# EbookReader_Schematic.net
KiCad netlist of a schematic drawn in EAGLE
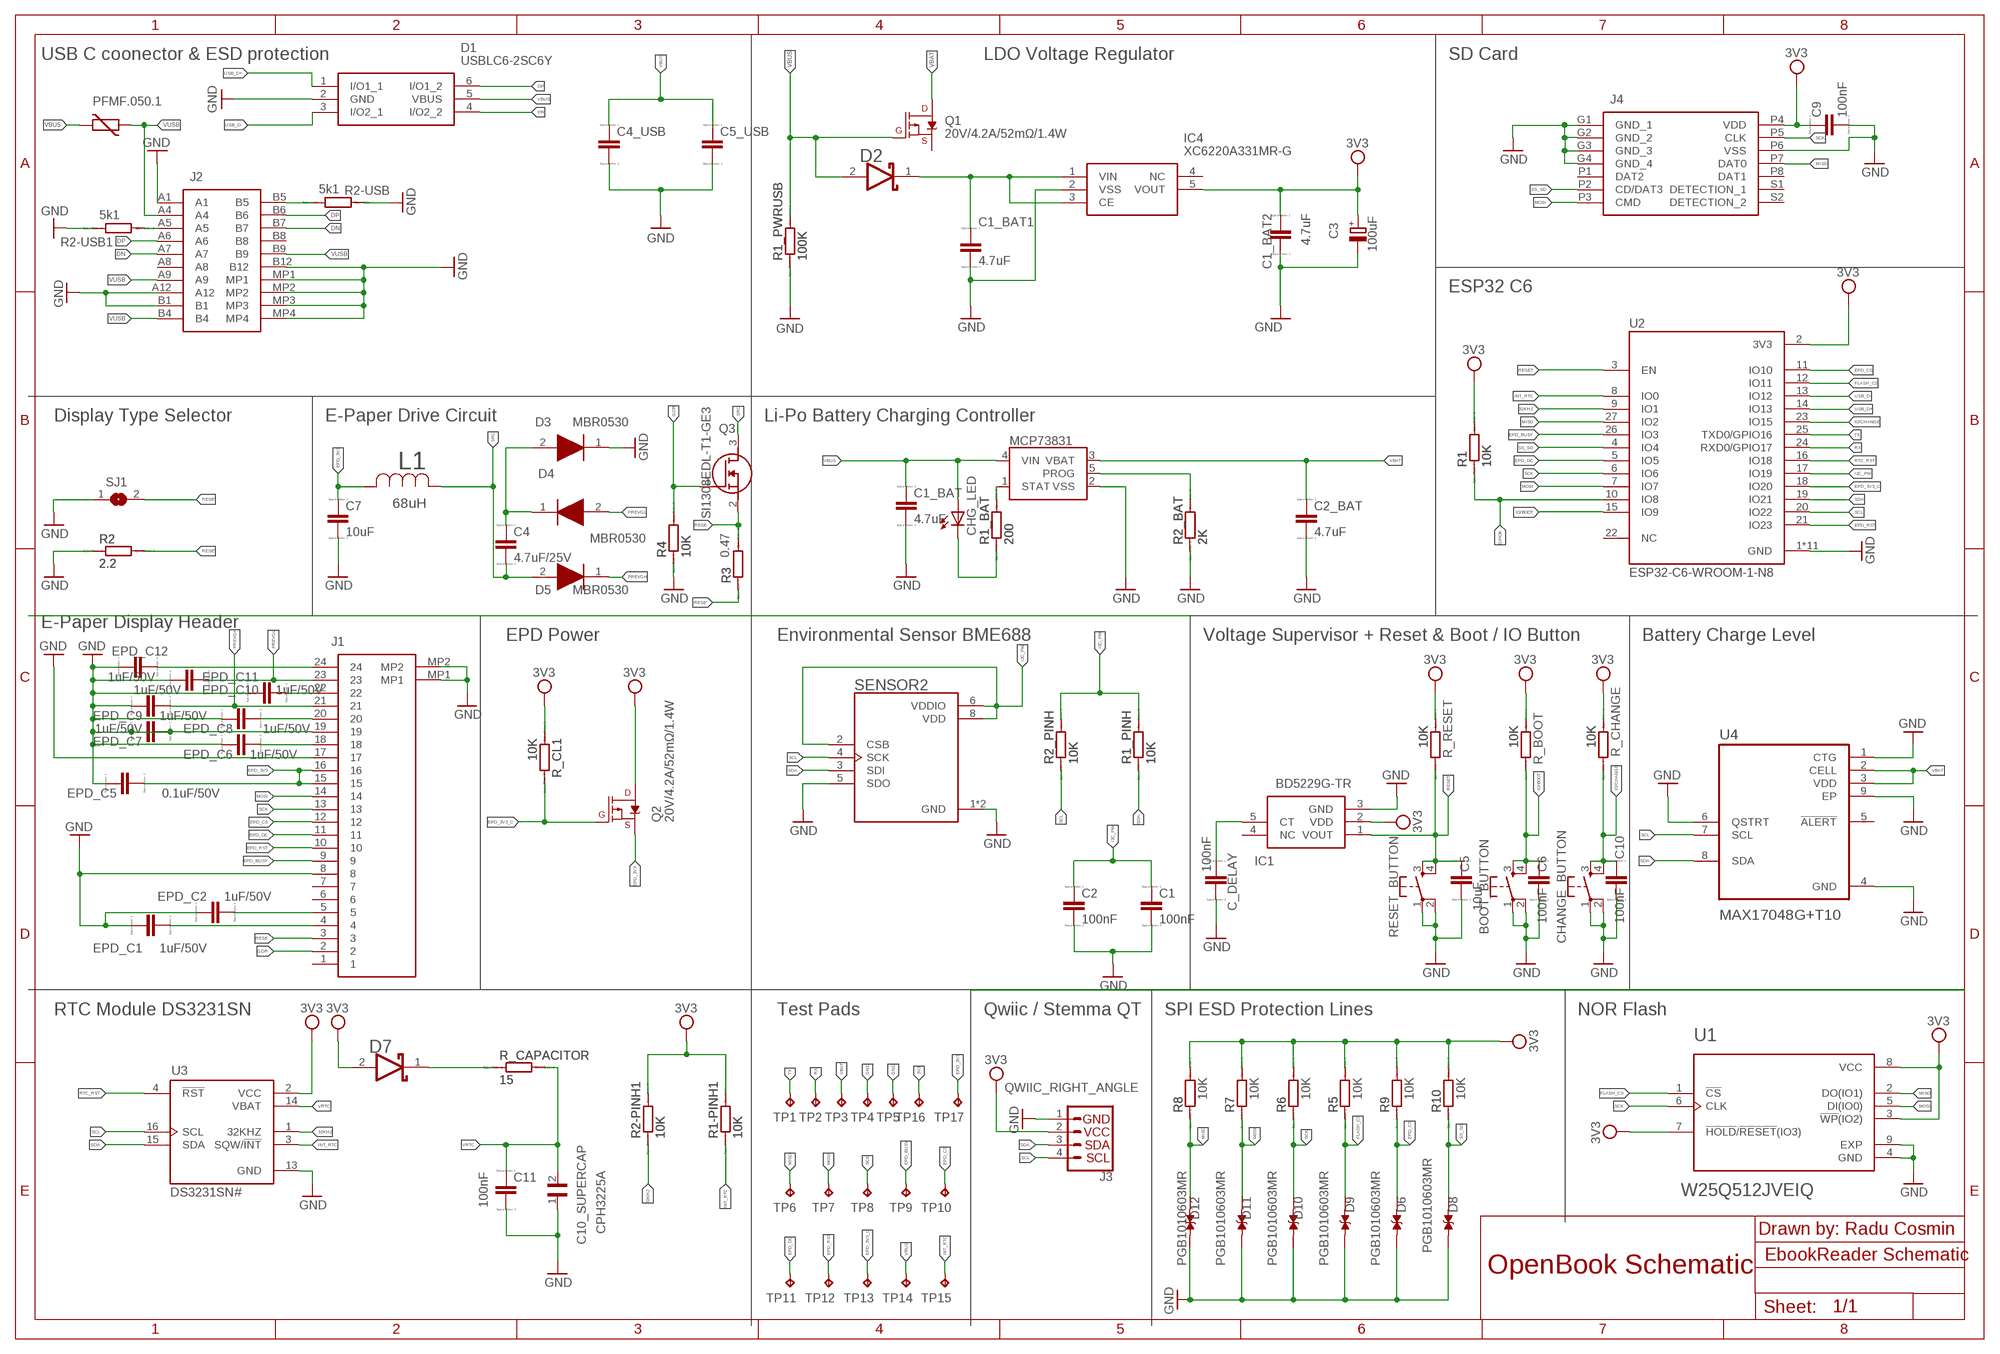
[diagram p0: schematic, sheet 1]

(export (version "E")
  (design (tool "Eeschema 10.0.6"))
  (components
    (comp (ref "BOOT_BUTTON")
      (value "BUTTON_CUSYOMV1")
      (footprint "eagle-import:MYBUTTON")
      (libsource (lib "eagle-import") (part "BUTTON_CUSYOMV1"))
    )
    (comp (ref "C1")
      (value "100nF")
      (footprint "eagle-import:ESP32_WROVER_EAGLE-LTSPICE_C0402")
      (libsource (lib "eagle-import") (part "ESP32_WROVER_EAGLE-LTSPICE_CC0402"))
    )
    (comp (ref "C1_BAT")
      (value "4.7uF")
      (footprint "eagle-import:ESP32_WROVER_EAGLE-LTSPICE_C0402")
      (libsource (lib "eagle-import") (part "ESP32_WROVER_EAGLE-LTSPICE_CC0402"))
    )
    (comp (ref "C1_BAT1")
      (value "4.7uF")
      (footprint "eagle-import:ESP32_WROVER_EAGLE-LTSPICE_C0402")
      (libsource (lib "eagle-import") (part "ESP32_WROVER_EAGLE-LTSPICE_CC0402"))
    )
    (comp (ref "C1_BAT2")
      (value "4.7uF")
      (footprint "eagle-import:ESP32_WROVER_EAGLE-LTSPICE_C0402")
      (libsource (lib "eagle-import") (part "ESP32_WROVER_EAGLE-LTSPICE_CC0402"))
    )
    (comp (ref "C2")
      (value "100nF")
      (footprint "eagle-import:ESP32_WROVER_EAGLE-LTSPICE_C0402")
      (libsource (lib "eagle-import") (part "ESP32_WROVER_EAGLE-LTSPICE_CC0402"))
    )
    (comp (ref "C2_BAT")
      (value "4.7uF")
      (footprint "eagle-import:ESP32_WROVER_EAGLE-LTSPICE_C0402")
      (libsource (lib "eagle-import") (part "ESP32_WROVER_EAGLE-LTSPICE_CC0402"))
    )
    (comp (ref "C3")
      (value "100uF")
      (footprint "eagle-import:RCL_CT3528")
      (libsource (lib "eagle-import") (part "RCL_CPOL-EUCT3528"))
    )
    (comp (ref "C4")
      (value "4.7uF/25V")
      (footprint "eagle-import:ESP32_WROVER_EAGLE-LTSPICE_C0402")
      (libsource (lib "eagle-import") (part "ESP32_WROVER_EAGLE-LTSPICE_CC0402"))
    )
    (comp (ref "C4_USB")
      (value "ESP32_WROVER_EAGLE-LTSPICE_CC0402")
      (footprint "eagle-import:ESP32_WROVER_EAGLE-LTSPICE_C0402")
      (libsource (lib "eagle-import") (part "ESP32_WROVER_EAGLE-LTSPICE_CC0402"))
    )
    (comp (ref "C5")
      (value "10uF")
      (footprint "eagle-import:ESP32_WROVER_EAGLE-LTSPICE_C0402")
      (libsource (lib "eagle-import") (part "ESP32_WROVER_EAGLE-LTSPICE_CC0402"))
    )
    (comp (ref "C5_USB")
      (value "ESP32_WROVER_EAGLE-LTSPICE_CC0402")
      (footprint "eagle-import:ESP32_WROVER_EAGLE-LTSPICE_C0402")
      (libsource (lib "eagle-import") (part "ESP32_WROVER_EAGLE-LTSPICE_CC0402"))
    )
    (comp (ref "C6")
      (value "100nF")
      (footprint "eagle-import:ESP32_WROVER_EAGLE-LTSPICE_C0402")
      (libsource (lib "eagle-import") (part "ESP32_WROVER_EAGLE-LTSPICE_CC0402"))
    )
    (comp (ref "C7")
      (value "10uF")
      (footprint "eagle-import:ESP32_WROVER_EAGLE-LTSPICE_C0402")
      (libsource (lib "eagle-import") (part "ESP32_WROVER_EAGLE-LTSPICE_CC0402"))
    )
    (comp (ref "C9")
      (value "100nF")
      (footprint "eagle-import:ESP32_WROVER_EAGLE-LTSPICE_C0402")
      (libsource (lib "eagle-import") (part "ESP32_WROVER_EAGLE-LTSPICE_CC0402"))
    )
    (comp (ref "C10")
      (value "100nF")
      (footprint "eagle-import:ESP32_WROVER_EAGLE-LTSPICE_C0402")
      (libsource (lib "eagle-import") (part "ESP32_WROVER_EAGLE-LTSPICE_CC0402"))
    )
    (comp (ref "C10_SUPERCAP")
      (value "CPH3225A")
      (footprint "eagle-import:CAPCP3225X100N")
      (fields (field (name "MF") "Seiko Instruments"))
      (libsource (lib "eagle-import") (part "CPH3225A"))
    )
    (comp (ref "C11")
      (value "100nF")
      (footprint "eagle-import:ESP32_WROVER_EAGLE-LTSPICE_C0402")
      (libsource (lib "eagle-import") (part "ESP32_WROVER_EAGLE-LTSPICE_CC0402"))
    )
    (comp (ref "CHANGE_BUTTON")
      (value "BUTTON_CUSYOMV1")
      (footprint "eagle-import:MYBUTTON")
      (libsource (lib "eagle-import") (part "BUTTON_CUSYOMV1"))
    )
    (comp (ref "CHG_LED")
      (value "ADAFRUIT_LEDCHIP-LED0603")
      (footprint "eagle-import:ADAFRUIT_CHIP-LED0603")
      (libsource (lib "eagle-import") (part "ADAFRUIT_LEDCHIP-LED0603"))
    )
    (comp (ref "C_DELAY")
      (value "100nF")
      (footprint "eagle-import:ESP32_WROVER_EAGLE-LTSPICE_C0402")
      (libsource (lib "eagle-import") (part "ESP32_WROVER_EAGLE-LTSPICE_CC0402"))
    )
    (comp (ref "D1")
      (value "USBLC6-2SC6Y")
      (footprint "eagle-import:SOT95P280X145-6N")
      (fields (field (name "MF") "STMicroelectronics"))
      (libsource (lib "eagle-import") (part "USBLC6-2SC6Y"))
    )
    (comp (ref "D2")
      (value "ESP32_WROVER_AVX---SD0805S020S1R0_AVX_SD0805S020S1R0_0_0AVX_SD0805S020S1R0_0_0")
      (footprint "eagle-import:ESP32_WROVER_AVX---SD0805S020S1R0_AVX_SD0805S020S1R0_0")
      (fields
        (field (name "DIGIKEY_PART_NUMBER") "478-7800-1-ND")
        (field (name "MF") "AVX")
        (field (name "MOUSER_PART_NUMBER") "581-SD0805S020S1R0")
      )
      (libsource (lib "eagle-import") (part "ESP32_WROVER_AVX---SD0805S020S1R0_AVX_SD0805S020S1R0_0_0AVX_SD0805S020S1R0_0_0"))
    )
    (comp (ref "D3")
      (value "MBR0530")
      (footprint "eagle-import:SOD3716X135N")
      (fields (field (name "MF") "ON Semiconductor"))
      (libsource (lib "eagle-import") (part "MBR0530"))
    )
    (comp (ref "D4")
      (value "MBR0530")
      (footprint "eagle-import:SOD3716X135N")
      (fields (field (name "MF") "ON Semiconductor"))
      (libsource (lib "eagle-import") (part "MBR0530"))
    )
    (comp (ref "D5")
      (value "MBR0530")
      (footprint "eagle-import:SOD3716X135N")
      (fields (field (name "MF") "ON Semiconductor"))
      (libsource (lib "eagle-import") (part "MBR0530"))
    )
    (comp (ref "D6")
      (value "PGB1010603MR")
      (footprint "eagle-import:DIOC1608X36N")
      (fields (field (name "MF") "Littelfuse Inc."))
      (libsource (lib "eagle-import") (part "PGB1010603MR"))
    )
    (comp (ref "D7")
      (value "ESP32_WROVER_AVX---SD0805S020S1R0_AVX_SD0805S020S1R0_0_0AVX_SD0805S020S1R0_0_0")
      (footprint "eagle-import:ESP32_WROVER_AVX---SD0805S020S1R0_AVX_SD0805S020S1R0_0")
      (fields
        (field (name "DIGIKEY_PART_NUMBER") "478-7800-1-ND")
        (field (name "MF") "AVX")
        (field (name "MOUSER_PART_NUMBER") "581-SD0805S020S1R0")
      )
      (libsource (lib "eagle-import") (part "ESP32_WROVER_AVX---SD0805S020S1R0_AVX_SD0805S020S1R0_0_0AVX_SD0805S020S1R0_0_0"))
    )
    (comp (ref "D8")
      (value "PGB1010603MR")
      (footprint "eagle-import:DIOC1608X36N")
      (fields (field (name "MF") "Littelfuse Inc."))
      (libsource (lib "eagle-import") (part "PGB1010603MR"))
    )
    (comp (ref "D9")
      (value "PGB1010603MR")
      (footprint "eagle-import:DIOC1608X36N")
      (fields (field (name "MF") "Littelfuse Inc."))
      (libsource (lib "eagle-import") (part "PGB1010603MR"))
    )
    (comp (ref "D10")
      (value "PGB1010603MR")
      (footprint "eagle-import:DIOC1608X36N")
      (fields (field (name "MF") "Littelfuse Inc."))
      (libsource (lib "eagle-import") (part "PGB1010603MR"))
    )
    (comp (ref "D11")
      (value "PGB1010603MR")
      (footprint "eagle-import:DIOC1608X36N")
      (fields (field (name "MF") "Littelfuse Inc."))
      (libsource (lib "eagle-import") (part "PGB1010603MR"))
    )
    (comp (ref "D12")
      (value "PGB1010603MR")
      (footprint "eagle-import:DIOC1608X36N")
      (fields (field (name "MF") "Littelfuse Inc."))
      (libsource (lib "eagle-import") (part "PGB1010603MR"))
    )
    (comp (ref "EPD_C1")
      (value "1uF/50V")
      (footprint "eagle-import:ESP32_WROVER_EAGLE-LTSPICE_C0402")
      (libsource (lib "eagle-import") (part "ESP32_WROVER_EAGLE-LTSPICE_CC0402"))
    )
    (comp (ref "EPD_C2")
      (value "1uF/50V")
      (footprint "eagle-import:ESP32_WROVER_EAGLE-LTSPICE_C0402")
      (libsource (lib "eagle-import") (part "ESP32_WROVER_EAGLE-LTSPICE_CC0402"))
    )
    (comp (ref "EPD_C5")
      (value "0.1uF/50V")
      (footprint "eagle-import:ESP32_WROVER_EAGLE-LTSPICE_C0402")
      (libsource (lib "eagle-import") (part "ESP32_WROVER_EAGLE-LTSPICE_CC0402"))
    )
    (comp (ref "EPD_C6")
      (value "1uF/50V")
      (footprint "eagle-import:ESP32_WROVER_EAGLE-LTSPICE_C0402")
      (libsource (lib "eagle-import") (part "ESP32_WROVER_EAGLE-LTSPICE_CC0402"))
    )
    (comp (ref "EPD_C7")
      (value "1uF/50V")
      (footprint "eagle-import:ESP32_WROVER_EAGLE-LTSPICE_C0402")
      (libsource (lib "eagle-import") (part "ESP32_WROVER_EAGLE-LTSPICE_CC0402"))
    )
    (comp (ref "EPD_C8")
      (value "1uF/50V")
      (footprint "eagle-import:ESP32_WROVER_EAGLE-LTSPICE_C0402")
      (libsource (lib "eagle-import") (part "ESP32_WROVER_EAGLE-LTSPICE_CC0402"))
    )
    (comp (ref "EPD_C9")
      (value "1uF/50V")
      (footprint "eagle-import:ESP32_WROVER_EAGLE-LTSPICE_C0402")
      (libsource (lib "eagle-import") (part "ESP32_WROVER_EAGLE-LTSPICE_CC0402"))
    )
    (comp (ref "EPD_C10")
      (value "1uF/50V")
      (footprint "eagle-import:ESP32_WROVER_EAGLE-LTSPICE_C0402")
      (libsource (lib "eagle-import") (part "ESP32_WROVER_EAGLE-LTSPICE_CC0402"))
    )
    (comp (ref "EPD_C11")
      (value "1uF/50V")
      (footprint "eagle-import:ESP32_WROVER_EAGLE-LTSPICE_C0402")
      (libsource (lib "eagle-import") (part "ESP32_WROVER_EAGLE-LTSPICE_CC0402"))
    )
    (comp (ref "EPD_C12")
      (value "1uF/50V")
      (footprint "eagle-import:ESP32_WROVER_EAGLE-LTSPICE_C0402")
      (libsource (lib "eagle-import") (part "ESP32_WROVER_EAGLE-LTSPICE_CC0402"))
    )
    (comp (ref "IC1")
      (value "BD5229G-TR")
      (footprint "eagle-import:SOT95P280X125-5N")
      (fields (field (name "MOUSER_PART_NUMBER") "755-BD5229G-TR"))
      (libsource (lib "eagle-import") (part "BD5229G-TR"))
    )
    (comp (ref "IC4")
      (value "XC6220A331MR-G")
      (footprint "eagle-import:SOT95P280X120-5N")
      (fields (field (name "MOUSER_PART_NUMBER") "865-XC6220A331MR-G"))
      (libsource (lib "eagle-import") (part "XC6220A331MR-G"))
    )
    (comp (ref "J1")
      (value "FH34SRJ-24S-0.5SH_99_")
      (footprint "eagle-import:FH34SRJ24S05SH99")
      (fields
        (field (name "MANUFACTURER_PART_NUMBER") "FH34SRJ-24S-0.5SH(99)")
        (field (name "MOUSER_PART_NUMBER") "798-FH34SRJ24S05SH99")
      )
      (libsource (lib "eagle-import") (part "FH34SRJ-24S-0.5SH_99_"))
    )
    (comp (ref "J2")
      (value "SAMACSYS_PARTS_USB4110-GF-A")
      (footprint "eagle-import:SAMACSYS_PARTS_USB4110GFA")
      (fields
        (field (name "MANUFACTURER_PART_NUMBER") "USB4110-GF-A")
        (field (name "MOUSER_PART_NUMBER") "640-USB4110-GF-A")
      )
      (libsource (lib "eagle-import") (part "SAMACSYS_PARTS_USB4110-GF-A"))
    )
    (comp (ref "J3")
      (value "QWIIC_RIGHT_ANGLE")
      (footprint "eagle-import:JST04_1MM_RA")
      (libsource (lib "eagle-import") (part "QWIIC_CONNECTORJS-1MM"))
    )
    (comp (ref "J4")
      (value "112A-TAAR-R03_ATTEND")
      (footprint "eagle-import:112ATAARR03ATTEND")
      (fields (field (name "MANUFACTURER_PART_NUMBER") "112A-TAAR-R03 ATTEND"))
      (libsource (lib "eagle-import") (part "112A-TAAR-R03_ATTEND"))
    )
    (comp (ref "L1")
      (value "68uH")
      (footprint "eagle-import:IND_4828-WE-TPC_WRE")
      (fields
        (field (name "MANUFACTURER_PART_NUMBER") "744043680")
        (field (name "COPYRIGHT") "Copyright (C) 2024 Ultra Librarian. All rights reserved.")
      )
      (libsource (lib "eagle-import") (part "744043680IND_4828-WE-TPC_WRE"))
    )
    (comp (ref "MCP73831")
      (value "ESP32_WROVER_SPARKFUN-IC-POWER_MCP73831")
      (footprint "eagle-import:ESP32_WROVER_SPARKFUN-IC-POWER_SOT23-5")
      (libsource (lib "eagle-import") (part "ESP32_WROVER_SPARKFUN-IC-POWER_MCP73831"))
    )
    (comp (ref "PFMF.050.1")
      (value "ESP32C6_VARISTORCN1812")
      (footprint "eagle-import:ESP32C6_VARISTOR_CT_CN1812")
      (libsource (lib "eagle-import") (part "ESP32C6_VARISTORCN1812"))
    )
    (comp (ref "Q1")
      (value "20V/4.2A/52mΩ/1.4W")
      (footprint "eagle-import:ESP32_WROVER_SPARKFUN-DISCRETESEMI_SOT23-3")
      (libsource (lib "eagle-import") (part "ESP32_WROVER_SPARKFUN-DISCRETESEMI_MOSFET_PCH-DMG2305UX-7"))
    )
    (comp (ref "Q2")
      (value "20V/4.2A/52mΩ/1.4W")
      (footprint "eagle-import:ESP32_WROVER_SPARKFUN-DISCRETESEMI_SOT23-3")
      (libsource (lib "eagle-import") (part "ESP32_WROVER_SPARKFUN-DISCRETESEMI_MOSFET_PCH-DMG2305UX-7"))
    )
    (comp (ref "Q3")
      (value "SI1308EDL-T1-GE3")
      (footprint "eagle-import:SOT65P210X110-3N")
      (fields (field (name "MF") "Vishay Siliconix"))
      (libsource (lib "eagle-import") (part "SI1308EDL-T1-GE3"))
    )
    (comp (ref "R1")
      (value "10K")
      (footprint "eagle-import:ESP32_WROVER_EAGLE-LTSPICE_R0402")
      (libsource (lib "eagle-import") (part "ESP32_WROVER_EAGLE-LTSPICE_RR0402"))
    )
    (comp (ref "R1-PINH1")
      (value "10K")
      (footprint "eagle-import:ESP32_WROVER_EAGLE-LTSPICE_R0402")
      (libsource (lib "eagle-import") (part "ESP32_WROVER_EAGLE-LTSPICE_RR0402"))
    )
    (comp (ref "R1_BAT")
      (value "200")
      (footprint "eagle-import:ESP32_WROVER_EAGLE-LTSPICE_R0402")
      (libsource (lib "eagle-import") (part "ESP32_WROVER_EAGLE-LTSPICE_RR0402"))
    )
    (comp (ref "R1_PINH")
      (value "10K")
      (footprint "eagle-import:ESP32_WROVER_EAGLE-LTSPICE_R0402")
      (libsource (lib "eagle-import") (part "ESP32_WROVER_EAGLE-LTSPICE_RR0402"))
    )
    (comp (ref "R1_PWRUSB")
      (value "100K")
      (footprint "eagle-import:ESP32_WROVER_EAGLE-LTSPICE_R0402")
      (libsource (lib "eagle-import") (part "ESP32_WROVER_EAGLE-LTSPICE_RR0402"))
    )
    (comp (ref "R2")
      (value "2.2")
      (footprint "eagle-import:ESP32_WROVER_EAGLE-LTSPICE_R0402")
      (libsource (lib "eagle-import") (part "ESP32_WROVER_EAGLE-LTSPICE_RR0402"))
    )
    (comp (ref "R2-PINH1")
      (value "10K")
      (footprint "eagle-import:ESP32_WROVER_EAGLE-LTSPICE_R0402")
      (libsource (lib "eagle-import") (part "ESP32_WROVER_EAGLE-LTSPICE_RR0402"))
    )
    (comp (ref "R2-USB")
      (value "5k1")
      (footprint "eagle-import:ESP32_WROVER_EAGLE-LTSPICE_R0402")
      (libsource (lib "eagle-import") (part "ESP32_WROVER_EAGLE-LTSPICE_RR0402"))
    )
    (comp (ref "R2-USB1")
      (value "5k1")
      (footprint "eagle-import:ESP32_WROVER_EAGLE-LTSPICE_R0402")
      (libsource (lib "eagle-import") (part "ESP32_WROVER_EAGLE-LTSPICE_RR0402"))
    )
    (comp (ref "R2_BAT")
      (value "2K")
      (footprint "eagle-import:ESP32_WROVER_EAGLE-LTSPICE_R0402")
      (libsource (lib "eagle-import") (part "ESP32_WROVER_EAGLE-LTSPICE_RR0402"))
    )
    (comp (ref "R2_PINH")
      (value "10K")
      (footprint "eagle-import:ESP32_WROVER_EAGLE-LTSPICE_R0402")
      (libsource (lib "eagle-import") (part "ESP32_WROVER_EAGLE-LTSPICE_RR0402"))
    )
    (comp (ref "R3")
      (value "0.47")
      (footprint "eagle-import:ESP32_WROVER_EAGLE-LTSPICE_R0402")
      (libsource (lib "eagle-import") (part "ESP32_WROVER_EAGLE-LTSPICE_RR0402"))
    )
    (comp (ref "R4")
      (value "10K")
      (footprint "eagle-import:ESP32_WROVER_EAGLE-LTSPICE_R0402")
      (libsource (lib "eagle-import") (part "ESP32_WROVER_EAGLE-LTSPICE_RR0402"))
    )
    (comp (ref "R5")
      (value "10K")
      (footprint "eagle-import:ESP32_WROVER_EAGLE-LTSPICE_R0402")
      (libsource (lib "eagle-import") (part "ESP32_WROVER_EAGLE-LTSPICE_RR0402"))
    )
    (comp (ref "R6")
      (value "10K")
      (footprint "eagle-import:ESP32_WROVER_EAGLE-LTSPICE_R0402")
      (libsource (lib "eagle-import") (part "ESP32_WROVER_EAGLE-LTSPICE_RR0402"))
    )
    (comp (ref "R7")
      (value "10K")
      (footprint "eagle-import:ESP32_WROVER_EAGLE-LTSPICE_R0402")
      (libsource (lib "eagle-import") (part "ESP32_WROVER_EAGLE-LTSPICE_RR0402"))
    )
    (comp (ref "R8")
      (value "10K")
      (footprint "eagle-import:ESP32_WROVER_EAGLE-LTSPICE_R0402")
      (libsource (lib "eagle-import") (part "ESP32_WROVER_EAGLE-LTSPICE_RR0402"))
    )
    (comp (ref "R9")
      (value "10K")
      (footprint "eagle-import:ESP32_WROVER_EAGLE-LTSPICE_R0402")
      (libsource (lib "eagle-import") (part "ESP32_WROVER_EAGLE-LTSPICE_RR0402"))
    )
    (comp (ref "R10")
      (value "10K")
      (footprint "eagle-import:ESP32_WROVER_EAGLE-LTSPICE_R0402")
      (libsource (lib "eagle-import") (part "ESP32_WROVER_EAGLE-LTSPICE_RR0402"))
    )
    (comp (ref "RESET_BUTTON")
      (value "BUTTON_CUSYOMV1")
      (footprint "eagle-import:MYBUTTON")
      (libsource (lib "eagle-import") (part "BUTTON_CUSYOMV1"))
    )
    (comp (ref "R_BOOT")
      (value "10K")
      (footprint "eagle-import:ESP32_WROVER_EAGLE-LTSPICE_R0402")
      (libsource (lib "eagle-import") (part "ESP32_WROVER_EAGLE-LTSPICE_RR0402"))
    )
    (comp (ref "R_CAPACITOR")
      (value "15")
      (footprint "eagle-import:ESP32_WROVER_EAGLE-LTSPICE_R0402")
      (libsource (lib "eagle-import") (part "ESP32_WROVER_EAGLE-LTSPICE_RR0402"))
    )
    (comp (ref "R_CHANGE")
      (value "10K")
      (footprint "eagle-import:ESP32_WROVER_EAGLE-LTSPICE_R0402")
      (libsource (lib "eagle-import") (part "ESP32_WROVER_EAGLE-LTSPICE_RR0402"))
    )
    (comp (ref "R_CL1")
      (value "10K")
      (footprint "eagle-import:ESP32_WROVER_EAGLE-LTSPICE_R0402")
      (libsource (lib "eagle-import") (part "ESP32_WROVER_EAGLE-LTSPICE_RR0402"))
    )
    (comp (ref "R_RESET")
      (value "10K")
      (footprint "eagle-import:ESP32_WROVER_EAGLE-LTSPICE_R0402")
      (libsource (lib "eagle-import") (part "ESP32_WROVER_EAGLE-LTSPICE_RR0402"))
    )
    (comp (ref "SENSOR2")
      (value "ESP32_WROVER_BME680_BME680")
      (footprint "eagle-import:ESP32_WROVER_BME680_PSON80P300X300X100-8N")
      (fields (field (name "MF") "Bosch Sensortec") (field (name "MP") "BME680"))
      (libsource (lib "eagle-import") (part "ESP32_WROVER_BME680_BME680"))
    )
    (comp (ref "SJ1") (value "SJ") (footprint "eagle-import:SJ") (libsource (lib "eagle-import") (part "SJ")))
    (comp (ref "TP1")
      (value "TPTP20R")
      (footprint "eagle-import:TP20R")
      (libsource (lib "eagle-import") (part "TPTP20R"))
    )
    (comp (ref "TP2")
      (value "TPTP20R")
      (footprint "eagle-import:TP20R")
      (libsource (lib "eagle-import") (part "TPTP20R"))
    )
    (comp (ref "TP3")
      (value "TPTP20R")
      (footprint "eagle-import:TP20R")
      (libsource (lib "eagle-import") (part "TPTP20R"))
    )
    (comp (ref "TP4")
      (value "TPTP20R")
      (footprint "eagle-import:TP20R")
      (libsource (lib "eagle-import") (part "TPTP20R"))
    )
    (comp (ref "TP5")
      (value "TPTP20R")
      (footprint "eagle-import:TP20R")
      (libsource (lib "eagle-import") (part "TPTP20R"))
    )
    (comp (ref "TP6")
      (value "TPTP20R")
      (footprint "eagle-import:TP20R")
      (libsource (lib "eagle-import") (part "TPTP20R"))
    )
    (comp (ref "TP7")
      (value "TPTP20R")
      (footprint "eagle-import:TP20R")
      (libsource (lib "eagle-import") (part "TPTP20R"))
    )
    (comp (ref "TP8")
      (value "TPTP20R")
      (footprint "eagle-import:TP20R")
      (libsource (lib "eagle-import") (part "TPTP20R"))
    )
    (comp (ref "TP9")
      (value "TPTP20R")
      (footprint "eagle-import:TP20R")
      (libsource (lib "eagle-import") (part "TPTP20R"))
    )
    (comp (ref "TP10")
      (value "TPTP20R")
      (footprint "eagle-import:TP20R")
      (libsource (lib "eagle-import") (part "TPTP20R"))
    )
    (comp (ref "TP11")
      (value "TPTP20R")
      (footprint "eagle-import:TP20R")
      (libsource (lib "eagle-import") (part "TPTP20R"))
    )
    (comp (ref "TP12")
      (value "TPTP20R")
      (footprint "eagle-import:TP20R")
      (libsource (lib "eagle-import") (part "TPTP20R"))
    )
    (comp (ref "TP13")
      (value "TPTP20R")
      (footprint "eagle-import:TP20R")
      (libsource (lib "eagle-import") (part "TPTP20R"))
    )
    (comp (ref "TP14")
      (value "TPTP20R")
      (footprint "eagle-import:TP20R")
      (libsource (lib "eagle-import") (part "TPTP20R"))
    )
    (comp (ref "TP15")
      (value "TPTP20R")
      (footprint "eagle-import:TP20R")
      (libsource (lib "eagle-import") (part "TPTP20R"))
    )
    (comp (ref "TP16")
      (value "TPTP20R")
      (footprint "eagle-import:TP20R")
      (libsource (lib "eagle-import") (part "TPTP20R"))
    )
    (comp (ref "TP17")
      (value "TPTP20R")
      (footprint "eagle-import:TP20R")
      (libsource (lib "eagle-import") (part "TPTP20R"))
    )
    (comp (ref "U1")
      (value "W25Q512JVEIQ")
      (footprint "eagle-import:SON127P600X800X80-9N")
      (fields (field (name "MF") "Winbond Electronics"))
      (libsource (lib "eagle-import") (part "W25Q512JVEIQ"))
    )
    (comp (ref "U2")
      (value "ESP32-C6-WROOM-1-N8")
      (footprint "eagle-import:XCVR_ESP32-C6-WROOM-1-N8")
      (fields (field (name "MF") "Espressif Systems"))
      (libsource (lib "eagle-import") (part "ESP32-C6-WROOM-1-N8"))
    )
    (comp (ref "U3")
      (value "DS3231SN#")
      (footprint "eagle-import:SOIC127P1032X265-16N")
      (fields (field (name "MF") "Analog Devices"))
      (libsource (lib "eagle-import") (part "DS3231SN#"))
    )
    (comp (ref "U4")
      (value "MAX17048G+T10")
      (footprint "eagle-import:SON50P200X200X80-9N")
      (fields (field (name "MF") "Analog Devices"))
      (libsource (lib "eagle-import") (part "MAX17048G+T10"))
    )
  )
  (nets
    (net (code "1") (name "3V3") (class "Default")
      (node (ref "C1_BAT2") (pin "1") (pinfunction "1_1") (pintype "passive"))
      (node (ref "C3") (pin "+") (pinfunction "+_+") (pintype "passive"))
      (node (ref "C9") (pin "1") (pinfunction "1_1") (pintype "passive"))
      (node (ref "D7") (pin "2") (pinfunction "ANODE_2") (pintype "bidirectional"))
      (node (ref "IC1") (pin "2") (pinfunction "VDD_2") (pintype "bidirectional"))
      (node (ref "IC4") (pin "5") (pinfunction "VOUT_5") (pintype "bidirectional"))
      (node (ref "J3") (pin "2") (pinfunction "2_2") (pintype "power_in"))
      (node (ref "J4") (pin "P4") (pinfunction "VDD_P4") (pintype "bidirectional"))
      (node (ref "Q2") (pin "3") (pinfunction "D_3") (pintype "bidirectional"))
      (node (ref "R1") (pin "2") (pinfunction "2_2") (pintype "passive"))
      (node (ref "R1-PINH1") (pin "2") (pinfunction "2_2") (pintype "passive"))
      (node (ref "R10") (pin "2") (pinfunction "2_2") (pintype "passive"))
      (node (ref "R2-PINH1") (pin "2") (pinfunction "2_2") (pintype "passive"))
      (node (ref "R5") (pin "2") (pinfunction "2_2") (pintype "passive"))
      (node (ref "R6") (pin "2") (pinfunction "2_2") (pintype "passive"))
      (node (ref "R7") (pin "2") (pinfunction "2_2") (pintype "passive"))
      (node (ref "R8") (pin "2") (pinfunction "2_2") (pintype "passive"))
      (node (ref "R9") (pin "2") (pinfunction "2_2") (pintype "passive"))
      (node (ref "R_BOOT") (pin "1") (pinfunction "1_1") (pintype "passive"))
      (node (ref "R_CHANGE") (pin "1") (pinfunction "1_1") (pintype "passive"))
      (node (ref "R_CL1") (pin "1") (pinfunction "1_1") (pintype "passive"))
      (node (ref "R_RESET") (pin "1") (pinfunction "1_1") (pintype "passive"))
      (node (ref "TP16") (pin "TP") (pinfunction "TP_TP") (pintype "input"))
      (node (ref "U1") (pin "3") (pinfunction "~{WP}(IO2)_3") (pintype "bidirectional"))
      (node (ref "U1") (pin "7") (pinfunction "~{HOLD}/~{RESET}(IO3)_7") (pintype "bidirectional"))
      (node (ref "U1") (pin "8") (pinfunction "VCC_8") (pintype "power_in"))
      (node (ref "U2") (pin "2") (pinfunction "3V3_2") (pintype "power_in"))
      (node (ref "U3") (pin "2") (pinfunction "VCC_2") (pintype "power_in"))
    )
    (net (code "2") (name "32KHZ") (class "Default")
      (node (ref "R2-PINH1") (pin "1") (pinfunction "1_1") (pintype "passive"))
      (node (ref "U2") (pin "9") (pinfunction "IO1_9") (pintype "bidirectional"))
      (node (ref "U3") (pin "1") (pinfunction "32KHZ_1") (pintype "output"))
    )
    (net (code "3") (name "DN") (class "Default")
      (node (ref "D1") (pin "4") (pinfunction "I/O2_2_4") (pintype "bidirectional"))
      (node (ref "J2") (pin "A7") (pinfunction "A7_A7") (pintype "bidirectional"))
      (node (ref "J2") (pin "B7") (pinfunction "B7_B7") (pintype "bidirectional"))
    )
    (net (code "4") (name "DP") (class "Default")
      (node (ref "D1") (pin "6") (pinfunction "I/O1_2_6") (pintype "bidirectional"))
      (node (ref "J2") (pin "A6") (pinfunction "A6_A6") (pintype "bidirectional"))
      (node (ref "J2") (pin "B6") (pinfunction "B6_B6") (pintype "bidirectional"))
    )
    (net (code "5") (name "EPD_3V3") (class "Default")
      (node (ref "C7") (pin "1") (pinfunction "1_1") (pintype "passive"))
      (node (ref "EPD_C5") (pin "2") (pinfunction "2_2") (pintype "passive"))
      (node (ref "J1") (pin "15") (pinfunction "15_15") (pintype "bidirectional"))
      (node (ref "J1") (pin "16") (pinfunction "16_16") (pintype "bidirectional"))
      (node (ref "L1") (pin "2") (pinfunction "2_2") (pintype "passive"))
      (node (ref "Q2") (pin "2") (pinfunction "S_2") (pintype "bidirectional"))
      (node (ref "TP17") (pin "TP") (pinfunction "TP_TP") (pintype "input"))
    )
    (net (code "6") (name "EPD_3V3_C") (class "Default")
      (node (ref "Q2") (pin "1") (pinfunction "G_1") (pintype "bidirectional"))
      (node (ref "R_CL1") (pin "2") (pinfunction "2_2") (pintype "passive"))
      (node (ref "TP13") (pin "TP") (pinfunction "TP_TP") (pintype "input"))
      (node (ref "U2") (pin "18") (pinfunction "IO20_18") (pintype "bidirectional"))
    )
    (net (code "7") (name "EPD_BUSY") (class "Default")
      (node (ref "J1") (pin "9") (pinfunction "9_9") (pintype "bidirectional"))
      (node (ref "TP9") (pin "TP") (pinfunction "TP_TP") (pintype "input"))
      (node (ref "U2") (pin "26") (pinfunction "IO3_26") (pintype "bidirectional"))
    )
    (net (code "8") (name "EPD_CS") (class "Default")
      (node (ref "D6") (pin "1") (pinfunction "1_1") (pintype "passive"))
      (node (ref "J1") (pin "12") (pinfunction "12_12") (pintype "bidirectional"))
      (node (ref "R9") (pin "1") (pinfunction "1_1") (pintype "passive"))
      (node (ref "TP10") (pin "TP") (pinfunction "TP_TP") (pintype "input"))
      (node (ref "U2") (pin "11") (pinfunction "IO10_11") (pintype "bidirectional"))
    )
    (net (code "9") (name "EPD_DC") (class "Default")
      (node (ref "J1") (pin "11") (pinfunction "11_11") (pintype "bidirectional"))
      (node (ref "TP11") (pin "TP") (pinfunction "TP_TP") (pintype "input"))
      (node (ref "U2") (pin "5") (pinfunction "IO5_5") (pintype "bidirectional"))
    )
    (net (code "10") (name "EPD_RST") (class "Default")
      (node (ref "J1") (pin "10") (pinfunction "10_10") (pintype "bidirectional"))
      (node (ref "TP12") (pin "TP") (pinfunction "TP_TP") (pintype "input"))
      (node (ref "U2") (pin "21") (pinfunction "IO23_21") (pintype "bidirectional"))
    )
    (net (code "11") (name "FLASH_CS") (class "Default")
      (node (ref "D9") (pin "1") (pinfunction "1_1") (pintype "passive"))
      (node (ref "R5") (pin "1") (pinfunction "1_1") (pintype "passive"))
      (node (ref "U1") (pin "1") (pinfunction "~{CS}_1") (pintype "input"))
      (node (ref "U2") (pin "12") (pinfunction "IO11_12") (pintype "bidirectional"))
    )
    (net (code "12") (name "GDR") (class "Default")
      (node (ref "J1") (pin "2") (pinfunction "2_2") (pintype "bidirectional"))
      (node (ref "Q3") (pin "1") (pinfunction "G_1") (pintype "bidirectional"))
      (node (ref "R4") (pin "2") (pinfunction "2_2") (pintype "passive"))
    )
    (net (code "13") (name "GND") (class "Default")
      (node (ref "BOOT_BUTTON") (pin "1") (pinfunction "1_1") (pintype "passive"))
      (node (ref "BOOT_BUTTON") (pin "2") (pinfunction "2_2") (pintype "passive"))
      (node (ref "C1") (pin "2") (pinfunction "2_2") (pintype "passive"))
      (node (ref "C10") (pin "2") (pinfunction "2_2") (pintype "passive"))
      (node (ref "C10_SUPERCAP") (pin "1") (pinfunction "1_1") (pintype "passive"))
      (node (ref "C11") (pin "2") (pinfunction "2_2") (pintype "passive"))
      (node (ref "C1_BAT") (pin "2") (pinfunction "2_2") (pintype "passive"))
      (node (ref "C1_BAT1") (pin "2") (pinfunction "2_2") (pintype "passive"))
      (node (ref "C1_BAT2") (pin "2") (pinfunction "2_2") (pintype "passive"))
      (node (ref "C2") (pin "2") (pinfunction "2_2") (pintype "passive"))
      (node (ref "C2_BAT") (pin "2") (pinfunction "2_2") (pintype "passive"))
      (node (ref "C3") (pin "-") (pinfunction "-_-") (pintype "passive"))
      (node (ref "C4_USB") (pin "2") (pinfunction "2_2") (pintype "passive"))
      (node (ref "C5") (pin "2") (pinfunction "2_2") (pintype "passive"))
      (node (ref "C5_USB") (pin "2") (pinfunction "2_2") (pintype "passive"))
      (node (ref "C6") (pin "2") (pinfunction "2_2") (pintype "passive"))
      (node (ref "C7") (pin "2") (pinfunction "2_2") (pintype "passive"))
      (node (ref "C9") (pin "2") (pinfunction "2_2") (pintype "passive"))
      (node (ref "CHANGE_BUTTON") (pin "1") (pinfunction "1_1") (pintype "passive"))
      (node (ref "CHANGE_BUTTON") (pin "2") (pinfunction "2_2") (pintype "passive"))
      (node (ref "C_DELAY") (pin "2") (pinfunction "2_2") (pintype "passive"))
      (node (ref "D1") (pin "2") (pinfunction "GND_2") (pintype "bidirectional"))
      (node (ref "D10") (pin "2") (pinfunction "2_2") (pintype "passive"))
      (node (ref "D11") (pin "2") (pinfunction "2_2") (pintype "passive"))
      (node (ref "D12") (pin "2") (pinfunction "2_2") (pintype "passive"))
      (node (ref "D3") (pin "1") (pinfunction "K_1") (pintype "bidirectional"))
      (node (ref "D6") (pin "2") (pinfunction "2_2") (pintype "passive"))
      (node (ref "D8") (pin "2") (pinfunction "2_2") (pintype "passive"))
      (node (ref "D9") (pin "2") (pinfunction "2_2") (pintype "passive"))
      (node (ref "EPD_C1") (pin "1") (pinfunction "1_1") (pintype "passive"))
      (node (ref "EPD_C10") (pin "1") (pinfunction "1_1") (pintype "passive"))
      (node (ref "EPD_C11") (pin "1") (pinfunction "1_1") (pintype "passive"))
      (node (ref "EPD_C12") (pin "1") (pinfunction "1_1") (pintype "passive"))
      (node (ref "EPD_C2") (pin "1") (pinfunction "1_1") (pintype "passive"))
      (node (ref "EPD_C5") (pin "1") (pinfunction "1_1") (pintype "passive"))
      (node (ref "EPD_C6") (pin "1") (pinfunction "1_1") (pintype "passive"))
      (node (ref "EPD_C7") (pin "1") (pinfunction "1_1") (pintype "passive"))
      (node (ref "EPD_C7") (pin "2") (pinfunction "2_2") (pintype "passive"))
      (node (ref "EPD_C8") (pin "1") (pinfunction "1_1") (pintype "passive"))
      (node (ref "EPD_C9") (pin "1") (pinfunction "1_1") (pintype "passive"))
      (node (ref "IC1") (pin "3") (pinfunction "GND_3") (pintype "bidirectional"))
      (node (ref "IC4") (pin "2") (pinfunction "VSS_2") (pintype "bidirectional"))
      (node (ref "J1") (pin "17") (pinfunction "17_17") (pintype "bidirectional"))
      (node (ref "J1") (pin "19") (pinfunction "19_19") (pintype "bidirectional"))
      (node (ref "J1") (pin "8") (pinfunction "8_8") (pintype "bidirectional"))
      (node (ref "J1") (pin "MP1") (pinfunction "MP1_MP1") (pintype "bidirectional"))
      (node (ref "J1") (pin "MP2") (pinfunction "MP2_MP2") (pintype "bidirectional"))
      (node (ref "J2") (pin "A1") (pinfunction "A1_A1") (pintype "bidirectional"))
      (node (ref "J2") (pin "A12") (pinfunction "A12_A12") (pintype "bidirectional"))
      (node (ref "J2") (pin "B1") (pinfunction "B1_B1") (pintype "bidirectional"))
      (node (ref "J2") (pin "B12") (pinfunction "B12_B12") (pintype "bidirectional"))
      (node (ref "J2") (pin "MP1") (pinfunction "MP1_MP1") (pintype "bidirectional"))
      (node (ref "J2") (pin "MP2") (pinfunction "MP2_MP2") (pintype "bidirectional"))
      (node (ref "J2") (pin "MP3") (pinfunction "MP3_MP3") (pintype "bidirectional"))
      (node (ref "J2") (pin "MP4") (pinfunction "MP4_MP4") (pintype "bidirectional"))
      (node (ref "J3") (pin "1") (pinfunction "1_1") (pintype "power_in"))
      (node (ref "J4") (pin "G1") (pinfunction "GND_1_G1") (pintype "bidirectional"))
      (node (ref "J4") (pin "G2") (pinfunction "GND_2_G2") (pintype "bidirectional"))
      (node (ref "J4") (pin "G3") (pinfunction "GND_3_G3") (pintype "bidirectional"))
      (node (ref "J4") (pin "G4") (pinfunction "GND_4_G4") (pintype "bidirectional"))
      (node (ref "J4") (pin "P6") (pinfunction "VSS_P6") (pintype "bidirectional"))
      (node (ref "MCP73831") (pin "2") (pinfunction "VSS_2") (pintype "power_in"))
      (node (ref "R1_PWRUSB") (pin "1") (pinfunction "1_1") (pintype "passive"))
      (node (ref "R2") (pin "1") (pinfunction "1_1") (pintype "passive"))
      (node (ref "R2-USB") (pin "2") (pinfunction "2_2") (pintype "passive"))
      (node (ref "R2-USB1") (pin "1") (pinfunction "1_1") (pintype "passive"))
      (node (ref "R2_BAT") (pin "1") (pinfunction "1_1") (pintype "passive"))
      (node (ref "R4") (pin "1") (pinfunction "1_1") (pintype "passive"))
      (node (ref "RESET_BUTTON") (pin "1") (pinfunction "1_1") (pintype "passive"))
      (node (ref "RESET_BUTTON") (pin "2") (pinfunction "2_2") (pintype "passive"))
      (node (ref "SENSOR2") (pin "1") (pinfunction "GND_1") (pintype "power_in"))
      (node (ref "SENSOR2") (pin "5") (pinfunction "SDO_5") (pintype "bidirectional"))
      (node (ref "SENSOR2") (pin "7") (pinfunction "GND_7") (pintype "power_in"))
      (node (ref "SJ1") (pin "1") (pinfunction "1_1") (pintype "passive"))
      (node (ref "TP4") (pin "TP") (pinfunction "TP_TP") (pintype "input"))
      (node (ref "TP5") (pin "TP") (pinfunction "TP_TP") (pintype "input"))
      (node (ref "U1") (pin "4") (pinfunction "GND_4") (pintype "power_in"))
      (node (ref "U1") (pin "9") (pinfunction "EXP_9") (pintype "passive"))
      (node (ref "U2") (pin "1") (pinfunction "GND_1") (pintype "power_in"))
      (node (ref "U2") (pin "28") (pinfunction "GND_28") (pintype "power_in"))
      (node (ref "U2") (pin "29_1") (pinfunction "GND_29_1") (pintype "power_in"))
      (node (ref "U2") (pin "29_2") (pinfunction "GND_29_2") (pintype "power_in"))
      (node (ref "U2") (pin "29_3") (pinfunction "GND_29_3") (pintype "power_in"))
      (node (ref "U2") (pin "29_4") (pinfunction "GND_29_4") (pintype "power_in"))
      (node (ref "U2") (pin "29_5") (pinfunction "GND_29_5") (pintype "power_in"))
      (node (ref "U2") (pin "29_6") (pinfunction "GND_29_6") (pintype "power_in"))
      (node (ref "U2") (pin "29_7") (pinfunction "GND_29_7") (pintype "power_in"))
      (node (ref "U2") (pin "29_8") (pinfunction "GND_29_8") (pintype "power_in"))
      (node (ref "U2") (pin "29_9") (pinfunction "GND_29_9") (pintype "power_in"))
      (node (ref "U3") (pin "13") (pinfunction "GND_13") (pintype "power_in"))
      (node (ref "U4") (pin "1") (pinfunction "CTG_1") (pintype "power_in"))
      (node (ref "U4") (pin "4") (pinfunction "GND_4") (pintype "power_in"))
      (node (ref "U4") (pin "6") (pinfunction "QSTRT_6") (pintype "input"))
      (node (ref "U4") (pin "9") (pinfunction "EP_9") (pintype "power_in"))
    )
    (net (code "14") (name "GPIO8") (class "Default")
      (node (ref "R1") (pin "1") (pinfunction "1_1") (pintype "passive"))
      (node (ref "U2") (pin "10") (pinfunction "IO8_10") (pintype "bidirectional"))
    )
    (net (code "15") (name "I2C_PW") (class "Default")
      (node (ref "C1") (pin "1") (pinfunction "1_1") (pintype "passive"))
      (node (ref "C2") (pin "1") (pinfunction "1_1") (pintype "passive"))
      (node (ref "R1_PINH") (pin "2") (pinfunction "2_2") (pintype "passive"))
      (node (ref "R2_PINH") (pin "2") (pinfunction "2_2") (pintype "passive"))
      (node (ref "SENSOR2") (pin "2") (pinfunction "CSB_2") (pintype "input"))
      (node (ref "SENSOR2") (pin "6") (pinfunction "VDDIO_6") (pintype "power_in"))
      (node (ref "SENSOR2") (pin "8") (pinfunction "VDD_8") (pintype "power_in"))
      (node (ref "U2") (pin "17") (pinfunction "IO19_17") (pintype "bidirectional"))
    )
    (net (code "16") (name "INT_RTC") (class "Default")
      (node (ref "R1-PINH1") (pin "1") (pinfunction "1_1") (pintype "passive"))
      (node (ref "TP15") (pin "TP") (pinfunction "TP_TP") (pintype "input"))
      (node (ref "U2") (pin "8") (pinfunction "IO0_8") (pintype "bidirectional"))
      (node (ref "U3") (pin "3") (pinfunction "SQW/~{INT}_3") (pintype "output"))
    )
    (net (code "17") (name "IO{slash}BOOT") (class "Default")
      (node (ref "BOOT_BUTTON") (pin "3") (pinfunction "3_3") (pintype "passive"))
      (node (ref "BOOT_BUTTON") (pin "4") (pinfunction "4_4") (pintype "passive"))
      (node (ref "C6") (pin "1") (pinfunction "1_1") (pintype "passive"))
      (node (ref "R_BOOT") (pin "2") (pinfunction "2_2") (pintype "passive"))
      (node (ref "U2") (pin "15") (pinfunction "IO9_15") (pintype "bidirectional"))
    )
    (net (code "18") (name "IO{slash}CHANGE") (class "Default")
      (node (ref "C10") (pin "1") (pinfunction "1_1") (pintype "passive"))
      (node (ref "CHANGE_BUTTON") (pin "3") (pinfunction "3_3") (pintype "passive"))
      (node (ref "CHANGE_BUTTON") (pin "4") (pinfunction "4_4") (pintype "passive"))
      (node (ref "R_CHANGE") (pin "2") (pinfunction "2_2") (pintype "passive"))
      (node (ref "U2") (pin "23") (pinfunction "IO15_23") (pintype "bidirectional"))
    )
    (net (code "19") (name "MISO") (class "Default")
      (node (ref "D12") (pin "1") (pinfunction "1_1") (pintype "passive"))
      (node (ref "J4") (pin "P7") (pinfunction "DAT0_P7") (pintype "bidirectional"))
      (node (ref "R8") (pin "1") (pinfunction "1_1") (pintype "passive"))
      (node (ref "TP6") (pin "TP") (pinfunction "TP_TP") (pintype "input"))
      (node (ref "U1") (pin "2") (pinfunction "DO(IO1)_2") (pintype "bidirectional"))
      (node (ref "U2") (pin "27") (pinfunction "IO2_27") (pintype "bidirectional"))
    )
    (net (code "20") (name "MOSI") (class "Default")
      (node (ref "D11") (pin "1") (pinfunction "1_1") (pintype "passive"))
      (node (ref "J1") (pin "14") (pinfunction "14_14") (pintype "bidirectional"))
      (node (ref "J4") (pin "P3") (pinfunction "CMD_P3") (pintype "bidirectional"))
      (node (ref "R7") (pin "1") (pinfunction "1_1") (pintype "passive"))
      (node (ref "TP7") (pin "TP") (pinfunction "TP_TP") (pintype "input"))
      (node (ref "U1") (pin "5") (pinfunction "DI(IO0)_5") (pintype "bidirectional"))
      (node (ref "U2") (pin "7") (pinfunction "IO7_7") (pintype "bidirectional"))
    )
    (net (code "21") (name "Net-(CHG_LED-PadC)") (class "Default")
      (node (ref "CHG_LED") (pin "C") (pinfunction "C_C") (pintype "passive"))
      (node (ref "R1_BAT") (pin "1") (pinfunction "1_1") (pintype "passive"))
    )
    (net (code "22") (name "Net-(D2-CATHODE)") (class "Default")
      (node (ref "C1_BAT1") (pin "1") (pinfunction "1_1") (pintype "passive"))
      (node (ref "D2") (pin "1") (pinfunction "CATHODE_1") (pintype "bidirectional"))
      (node (ref "IC4") (pin "1") (pinfunction "VIN_1") (pintype "bidirectional"))
      (node (ref "IC4") (pin "3") (pinfunction "CE_3") (pintype "bidirectional"))
    )
    (net (code "23") (name "Net-(D3-A)") (class "Default")
      (node (ref "C4") (pin "1") (pinfunction "1_1") (pintype "passive"))
      (node (ref "D3") (pin "2") (pinfunction "A_2") (pintype "bidirectional"))
      (node (ref "D4") (pin "1") (pinfunction "K_1") (pintype "bidirectional"))
    )
    (net (code "24") (name "Net-(D7-CATHODE)") (class "Default")
      (node (ref "D7") (pin "1") (pinfunction "CATHODE_1") (pintype "bidirectional"))
      (node (ref "R_CAPACITOR") (pin "1") (pinfunction "1_1") (pintype "passive"))
    )
    (net (code "25") (name "Net-(EPD_C1-Pad2)") (class "Default")
      (node (ref "EPD_C1") (pin "2") (pinfunction "2_2") (pintype "passive"))
      (node (ref "J1") (pin "4") (pinfunction "4_4") (pintype "bidirectional"))
    )
    (net (code "26") (name "Net-(EPD_C2-Pad2)") (class "Default")
      (node (ref "EPD_C2") (pin "2") (pinfunction "2_2") (pintype "passive"))
      (node (ref "J1") (pin "5") (pinfunction "5_5") (pintype "bidirectional"))
    )
    (net (code "27") (name "Net-(EPD_C6-Pad2)") (class "Default")
      (node (ref "EPD_C6") (pin "2") (pinfunction "2_2") (pintype "passive"))
      (node (ref "J1") (pin "18") (pinfunction "18_18") (pintype "bidirectional"))
    )
    (net (code "28") (name "Net-(EPD_C8-Pad2)") (class "Default")
      (node (ref "EPD_C8") (pin "2") (pinfunction "2_2") (pintype "passive"))
      (node (ref "J1") (pin "20") (pinfunction "20_20") (pintype "bidirectional"))
    )
    (net (code "29") (name "Net-(EPD_C10-Pad2)") (class "Default")
      (node (ref "EPD_C10") (pin "2") (pinfunction "2_2") (pintype "passive"))
      (node (ref "J1") (pin "22") (pinfunction "22_22") (pintype "bidirectional"))
    )
    (net (code "30") (name "Net-(EPD_C12-Pad2)") (class "Default")
      (node (ref "EPD_C12") (pin "2") (pinfunction "2_2") (pintype "passive"))
      (node (ref "J1") (pin "24") (pinfunction "24_24") (pintype "bidirectional"))
    )
    (net (code "31") (name "Net-(IC1-CT)") (class "Default")
      (node (ref "C_DELAY") (pin "1") (pinfunction "1_1") (pintype "passive"))
      (node (ref "IC1") (pin "5") (pinfunction "CT_5") (pintype "bidirectional"))
    )
    (net (code "32") (name "Net-(J2-PadA5)") (class "Default")
      (node (ref "J2") (pin "A5") (pinfunction "A5_A5") (pintype "bidirectional"))
      (node (ref "R2-USB1") (pin "2") (pinfunction "2_2") (pintype "passive"))
    )
    (net (code "33") (name "Net-(J2-PadB5)") (class "Default")
      (node (ref "J2") (pin "B5") (pinfunction "B5_B5") (pintype "bidirectional"))
      (node (ref "R2-USB") (pin "1") (pinfunction "1_1") (pintype "passive"))
    )
    (net (code "34") (name "Net-(MCP73831-PROG)") (class "Default")
      (node (ref "MCP73831") (pin "5") (pinfunction "PROG_5") (pintype "input"))
      (node (ref "R2_BAT") (pin "2") (pinfunction "2_2") (pintype "passive"))
    )
    (net (code "35") (name "Net-(MCP73831-STAT)") (class "Default")
      (node (ref "MCP73831") (pin "1") (pinfunction "STAT_1") (pintype "output"))
      (node (ref "R1_BAT") (pin "2") (pinfunction "2_2") (pintype "passive"))
    )
    (net (code "36") (name "PREVGH") (class "Default")
      (node (ref "D5") (pin "1") (pinfunction "K_1") (pintype "bidirectional"))
      (node (ref "EPD_C9") (pin "2") (pinfunction "2_2") (pintype "passive"))
      (node (ref "J1") (pin "21") (pinfunction "21_21") (pintype "bidirectional"))
    )
    (net (code "37") (name "PREVGL") (class "Default")
      (node (ref "D4") (pin "2") (pinfunction "A_2") (pintype "bidirectional"))
      (node (ref "EPD_C11") (pin "2") (pinfunction "2_2") (pintype "passive"))
      (node (ref "J1") (pin "23") (pinfunction "23_23") (pintype "bidirectional"))
    )
    (net (code "38") (name "RESE") (class "Default")
      (node (ref "J1") (pin "3") (pinfunction "3_3") (pintype "bidirectional"))
      (node (ref "Q3") (pin "2") (pinfunction "S_2") (pintype "bidirectional"))
      (node (ref "R3") (pin "2") (pinfunction "2_2") (pintype "passive"))
    )
    (net (code "39") (name "RESE'") (class "Default")
      (node (ref "R2") (pin "2") (pinfunction "2_2") (pintype "passive"))
      (node (ref "R3") (pin "1") (pinfunction "1_1") (pintype "passive"))
      (node (ref "SJ1") (pin "2") (pinfunction "2_2") (pintype "passive"))
    )
    (net (code "40") (name "RESET") (class "Default")
      (node (ref "C5") (pin "1") (pinfunction "1_1") (pintype "passive"))
      (node (ref "IC1") (pin "1") (pinfunction "VOUT_1") (pintype "bidirectional"))
      (node (ref "RESET_BUTTON") (pin "3") (pinfunction "3_3") (pintype "passive"))
      (node (ref "RESET_BUTTON") (pin "4") (pinfunction "4_4") (pintype "passive"))
      (node (ref "R_RESET") (pin "2") (pinfunction "2_2") (pintype "passive"))
      (node (ref "U2") (pin "3") (pinfunction "EN_3") (pintype "input"))
    )
    (net (code "41") (name "RTC_RST") (class "Default")
      (node (ref "U2") (pin "16") (pinfunction "IO18_16") (pintype "bidirectional"))
      (node (ref "U3") (pin "4") (pinfunction "~{RST}_4") (pintype "input"))
    )
    (net (code "42") (name "RX") (class "Default")
      (node (ref "TP2") (pin "TP") (pinfunction "TP_TP") (pintype "input"))
      (node (ref "U2") (pin "24") (pinfunction "RXD0/GPIO17_24") (pintype "bidirectional"))
    )
    (net (code "43") (name "SCK") (class "Default")
      (node (ref "D10") (pin "1") (pinfunction "1_1") (pintype "passive"))
      (node (ref "J1") (pin "13") (pinfunction "13_13") (pintype "bidirectional"))
      (node (ref "J4") (pin "P5") (pinfunction "CLK_P5") (pintype "bidirectional"))
      (node (ref "R6") (pin "1") (pinfunction "1_1") (pintype "passive"))
      (node (ref "TP8") (pin "TP") (pinfunction "TP_TP") (pintype "input"))
      (node (ref "U1") (pin "6") (pinfunction "CLK_6") (pintype "input"))
      (node (ref "U2") (pin "6") (pinfunction "IO6_6") (pintype "bidirectional"))
    )
    (net (code "44") (name "SCL") (class "Default")
      (node (ref "J3") (pin "4") (pinfunction "4_4") (pintype "passive"))
      (node (ref "R2_PINH") (pin "1") (pinfunction "1_1") (pintype "passive"))
      (node (ref "SENSOR2") (pin "4") (pinfunction "SCK_4") (pintype "input"))
      (node (ref "U2") (pin "20") (pinfunction "IO22_20") (pintype "bidirectional"))
      (node (ref "U3") (pin "16") (pinfunction "SCL_16") (pintype "input"))
      (node (ref "U4") (pin "7") (pinfunction "SCL_7") (pintype "input"))
    )
    (net (code "45") (name "SDA") (class "Default")
      (node (ref "J3") (pin "3") (pinfunction "3_3") (pintype "passive"))
      (node (ref "R1_PINH") (pin "1") (pinfunction "1_1") (pintype "passive"))
      (node (ref "SENSOR2") (pin "3") (pinfunction "SDI_3") (pintype "bidirectional"))
      (node (ref "U2") (pin "19") (pinfunction "IO21_19") (pintype "bidirectional"))
      (node (ref "U3") (pin "15") (pinfunction "SDA_15") (pintype "bidirectional"))
      (node (ref "U4") (pin "8") (pinfunction "SDA_8") (pintype "bidirectional"))
    )
    (net (code "46") (name "SRC") (class "Default")
      (node (ref "C4") (pin "2") (pinfunction "2_2") (pintype "passive"))
      (node (ref "D5") (pin "2") (pinfunction "A_2") (pintype "bidirectional"))
      (node (ref "L1") (pin "1") (pinfunction "1_1") (pintype "passive"))
      (node (ref "Q3") (pin "3") (pinfunction "D_3") (pintype "bidirectional"))
    )
    (net (code "47") (name "SS_SD") (class "Default")
      (node (ref "D8") (pin "1") (pinfunction "1_1") (pintype "passive"))
      (node (ref "J4") (pin "P2") (pinfunction "CD/DAT3_P2") (pintype "bidirectional"))
      (node (ref "R10") (pin "1") (pinfunction "1_1") (pintype "passive"))
      (node (ref "U2") (pin "4") (pinfunction "IO4_4") (pintype "bidirectional"))
    )
    (net (code "48") (name "TX") (class "Default")
      (node (ref "TP1") (pin "TP") (pinfunction "TP_TP") (pintype "input"))
      (node (ref "U2") (pin "25") (pinfunction "TXD0/GPIO16_25") (pintype "bidirectional"))
    )
    (net (code "49") (name "USB_D+") (class "Default")
      (node (ref "D1") (pin "1") (pinfunction "I/O1_1_1") (pintype "bidirectional"))
      (node (ref "U2") (pin "14") (pinfunction "IO13_14") (pintype "bidirectional"))
    )
    (net (code "50") (name "USB_D-") (class "Default")
      (node (ref "D1") (pin "3") (pinfunction "I/O2_1_3") (pintype "bidirectional"))
      (node (ref "U2") (pin "13") (pinfunction "IO12_13") (pintype "bidirectional"))
    )
    (net (code "51") (name "VBAT") (class "Default")
      (node (ref "C2_BAT") (pin "1") (pinfunction "1_1") (pintype "passive"))
      (node (ref "MCP73831") (pin "3") (pinfunction "VBAT_3") (pintype "power_in"))
      (node (ref "Q1") (pin "3") (pinfunction "D_3") (pintype "bidirectional"))
      (node (ref "TP3") (pin "TP") (pinfunction "TP_TP") (pintype "input"))
      (node (ref "U4") (pin "2") (pinfunction "CELL_2") (pintype "power_in"))
      (node (ref "U4") (pin "3") (pinfunction "VDD_3") (pintype "power_in"))
    )
    (net (code "52") (name "VBUS") (class "Default")
      (node (ref "C1_BAT") (pin "1") (pinfunction "1_1") (pintype "passive"))
      (node (ref "C4_USB") (pin "1") (pinfunction "1_1") (pintype "passive"))
      (node (ref "C5_USB") (pin "1") (pinfunction "1_1") (pintype "passive"))
      (node (ref "CHG_LED") (pin "A") (pinfunction "A_A") (pintype "passive"))
      (node (ref "D1") (pin "5") (pinfunction "VBUS_5") (pintype "bidirectional"))
      (node (ref "D2") (pin "2") (pinfunction "ANODE_2") (pintype "bidirectional"))
      (node (ref "MCP73831") (pin "4") (pinfunction "VIN_4") (pintype "power_in"))
      (node (ref "PFMF.050.1") (pin "2") (pinfunction "2_2") (pintype "passive"))
      (node (ref "Q1") (pin "1") (pinfunction "G_1") (pintype "bidirectional"))
      (node (ref "R1_PWRUSB") (pin "2") (pinfunction "2_2") (pintype "passive"))
      (node (ref "TP14") (pin "TP") (pinfunction "TP_TP") (pintype "input"))
    )
    (net (code "53") (name "VRTC") (class "Default")
      (node (ref "C10_SUPERCAP") (pin "2") (pinfunction "2_2") (pintype "passive"))
      (node (ref "C11") (pin "1") (pinfunction "1_1") (pintype "passive"))
      (node (ref "R_CAPACITOR") (pin "2") (pinfunction "2_2") (pintype "passive"))
      (node (ref "U3") (pin "14") (pinfunction "VBAT_14") (pintype "power_in"))
    )
    (net (code "54") (name "VUSB") (class "Default")
      (node (ref "J2") (pin "A4") (pinfunction "A4_A4") (pintype "bidirectional"))
      (node (ref "J2") (pin "A9") (pinfunction "A9_A9") (pintype "bidirectional"))
      (node (ref "J2") (pin "B4") (pinfunction "B4_B4") (pintype "bidirectional"))
      (node (ref "J2") (pin "B9") (pinfunction "B9_B9") (pintype "bidirectional"))
      (node (ref "PFMF.050.1") (pin "1") (pinfunction "1_1") (pintype "passive"))
    )
    (net (code "55") (name "unconnected-(IC1-NC-Pad4)") (class "Default")
      (node (ref "IC1") (pin "4") (pinfunction "NC_4") (pintype "no_connect"))
    )
    (net (code "56") (name "unconnected-(IC4-NC-Pad4)") (class "Default")
      (node (ref "IC4") (pin "4") (pinfunction "NC_4") (pintype "no_connect"))
    )
    (net (code "57") (name "unconnected-(J1-Pad1)") (class "Default")
      (node (ref "J1") (pin "1") (pinfunction "1_1") (pintype "bidirectional"))
    )
    (net (code "58") (name "unconnected-(J1-Pad6)") (class "Default")
      (node (ref "J1") (pin "6") (pinfunction "6_6") (pintype "bidirectional"))
    )
    (net (code "59") (name "unconnected-(J1-Pad7)") (class "Default")
      (node (ref "J1") (pin "7") (pinfunction "7_7") (pintype "bidirectional"))
    )
    (net (code "60") (name "unconnected-(J2-PadA8)") (class "Default")
      (node (ref "J2") (pin "A8") (pinfunction "A8_A8") (pintype "bidirectional"))
    )
    (net (code "61") (name "unconnected-(J2-PadB8)") (class "Default")
      (node (ref "J2") (pin "B8") (pinfunction "B8_B8") (pintype "bidirectional"))
    )
    (net (code "62") (name "unconnected-(J4-DAT1-PadP8)") (class "Default")
      (node (ref "J4") (pin "P8") (pinfunction "DAT1_P8") (pintype "bidirectional"))
    )
    (net (code "63") (name "unconnected-(J4-DAT2-PadP1)") (class "Default")
      (node (ref "J4") (pin "P1") (pinfunction "DAT2_P1") (pintype "bidirectional"))
    )
    (net (code "64") (name "unconnected-(J4-DETECTION_1-PadS1)") (class "Default")
      (node (ref "J4") (pin "S1") (pinfunction "DETECTION_1_S1") (pintype "bidirectional"))
    )
    (net (code "65") (name "unconnected-(J4-DETECTION_2-PadS2)") (class "Default")
      (node (ref "J4") (pin "S2") (pinfunction "DETECTION_2_S2") (pintype "bidirectional"))
    )
    (net (code "66") (name "unconnected-(Q1-S-Pad2)") (class "Default")
      (node (ref "Q1") (pin "2") (pinfunction "S_2") (pintype "bidirectional"))
    )
    (net (code "67") (name "unconnected-(U2-NC-Pad22)") (class "Default")
      (node (ref "U2") (pin "22") (pinfunction "NC_22") (pintype "no_connect"))
    )
    (net (code "68") (name "unconnected-(U4-~{ALERT}-Pad5)") (class "Default")
      (node (ref "U4") (pin "5") (pinfunction "~{ALERT}_5") (pintype "output"))
    )
  )
)
